# MPU.net
KiCad netlist of a schematic drawn in Altium Designer
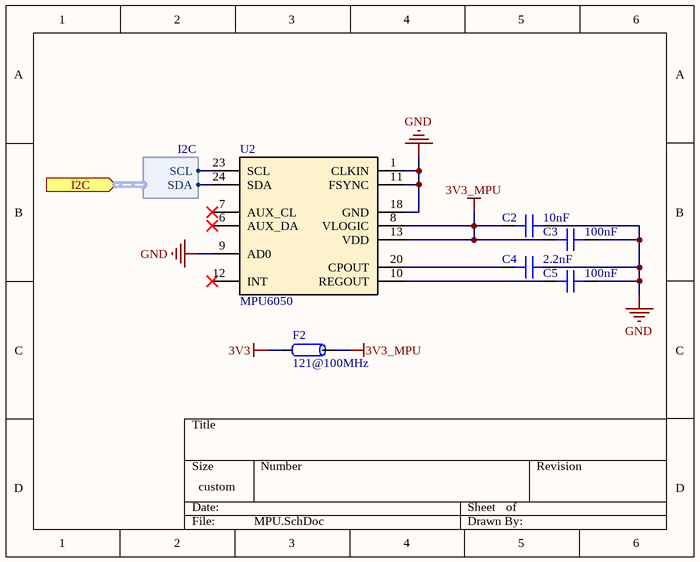
[diagram p0: MPU.SchDoc]

(export (version "E")
  (design (tool "Eeschema 10.0.6"))
  (components
    (comp (ref "C2")
      (value "10nF")
      (footprint "CAP 0603_1608")
      (description "SMT Capacitor")
      (libsource (lib "Capacitor") (part "Cap 0603"))
    )
    (comp (ref "C3")
      (value "100nF")
      (footprint "CAP 0603_1608")
      (description "SMT Capacitor")
      (libsource (lib "Capacitor") (part "Cap 0603"))
    )
    (comp (ref "C4")
      (value "2.2nF")
      (footprint "CAP 0603_1608")
      (description "SMT Capacitor")
      (libsource (lib "Capacitor") (part "Cap 0603"))
    )
    (comp (ref "C5")
      (value "100nF")
      (footprint "CAP 0603_1608")
      (description "SMT Capacitor")
      (libsource (lib "Capacitor") (part "Cap 0603"))
    )
    (comp (ref "F2")
      (value "121@100MHz")
      (footprint "Ferrite-0805")
      (description "Ferrite Bead")
      (libsource (lib "Salman_lib") (part "Ferrite Bead"))
    )
    (comp (ref "U2") (value "MPU6050") (footprint "QFN-24TA") (libsource (lib "Salman_lib") (part "MPU6050")))
  )
  (nets
    (net (code "2") (name "/SCL") (class "Default")
      (node (ref "U2") (pin "23") (pinfunction "SCL_23") (pintype "passive"))
    )
    (net (code "3") (name "/SDA") (class "Default")
      (node (ref "U2") (pin "24") (pinfunction "SDA_24") (pintype "passive"))
    )
    (net (code "5") (name "3V3") (class "Default")
      (node (ref "F2") (pin "1") (pinfunction "67_1") (pintype "passive"))
    )
    (net (code "6") (name "3V3_MPU") (class "Default")
      (node (ref "C2") (pin "2") (pinfunction "2_2") (pintype "passive"))
      (node (ref "C3") (pin "2") (pinfunction "2_2") (pintype "passive"))
      (node (ref "F2") (pin "2") (pinfunction "66_2") (pintype "passive"))
      (node (ref "U2") (pin "13") (pinfunction "VDD_13") (pintype "passive"))
      (node (ref "U2") (pin "8") (pinfunction "VLOGIC_8") (pintype "passive"))
    )
    (net (code "7") (name "GND") (class "Default")
      (node (ref "C2") (pin "1") (pinfunction "1_1") (pintype "passive"))
      (node (ref "C3") (pin "1") (pinfunction "1_1") (pintype "passive"))
      (node (ref "C4") (pin "2") (pinfunction "2_2") (pintype "passive"))
      (node (ref "C5") (pin "2") (pinfunction "2_2") (pintype "passive"))
      (node (ref "U2") (pin "1") (pinfunction "CLKIN_1") (pintype "passive"))
      (node (ref "U2") (pin "11") (pinfunction "FSYNC_11") (pintype "passive"))
      (node (ref "U2") (pin "18") (pinfunction "GND_18") (pintype "passive"))
      (node (ref "U2") (pin "9") (pinfunction "AD0_9") (pintype "passive"))
    )
    (net (code "8") (name "Net-(U2-CPOUT)") (class "Default")
      (node (ref "C4") (pin "1") (pinfunction "1_1") (pintype "passive"))
      (node (ref "U2") (pin "20") (pinfunction "CPOUT_20") (pintype "passive"))
    )
    (net (code "9") (name "Net-(U2-REGOUT)") (class "Default")
      (node (ref "C5") (pin "1") (pinfunction "1_1") (pintype "passive"))
      (node (ref "U2") (pin "10") (pinfunction "REGOUT_10") (pintype "passive"))
    )
    (net (code "10") (name "unconnected-(U2-AUX_CL-Pad7)") (class "Default")
      (node (ref "U2") (pin "7") (pinfunction "AUX_CL_7") (pintype "passive+no_connect"))
    )
    (net (code "11") (name "unconnected-(U2-AUX_DA-Pad6)") (class "Default")
      (node (ref "U2") (pin "6") (pinfunction "AUX_DA_6") (pintype "passive+no_connect"))
    )
    (net (code "12") (name "unconnected-(U2-INT-Pad12)") (class "Default")
      (node (ref "U2") (pin "12") (pinfunction "INT_12") (pintype "passive+no_connect"))
    )
  )
)
